# power.net
KiCad netlist of a schematic drawn in Altium Designer
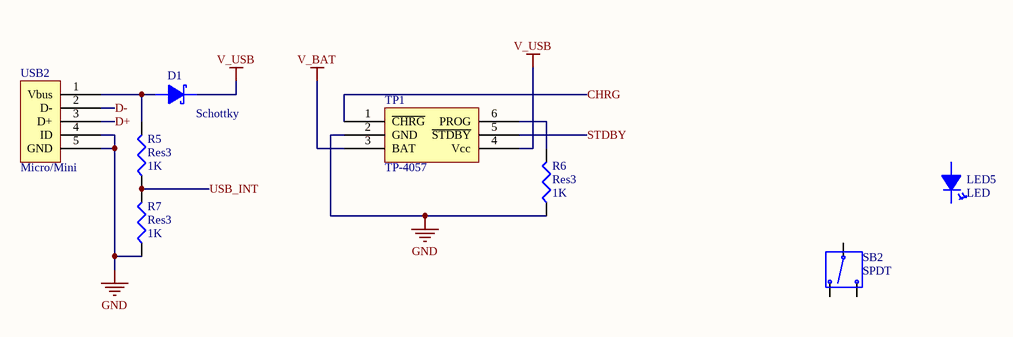
[diagram p0: power.SchDoc]

(export (version "E")
  (design (tool "Eeschema 10.0.6"))
  (components
    (comp (ref "D1") (value "Schottky") (footprint "SOD-523") (libsource (lib "ZGR") (part "Diode2")))
    (comp (ref "LED5") (value "LED") (footprint "LED_3mm_DIP") (libsource (lib "ZGR") (part "LED")))
    (comp (ref "R5")
      (value "Res3")
      (footprint "J1-0603")
      (description "Resistor")
      (fields (field (name "ALTIUM_VALUE") "1K") (field (name "PUBLISHER") "Altium Limited"))
      (libsource (lib "Miscellaneous Devices") (part "Res3"))
    )
    (comp (ref "R6")
      (value "Res3")
      (footprint "J1-0603")
      (description "Resistor")
      (fields (field (name "ALTIUM_VALUE") "1K") (field (name "PUBLISHER") "Altium Limited"))
      (libsource (lib "Miscellaneous Devices") (part "Res3"))
    )
    (comp (ref "R7")
      (value "Res3")
      (footprint "J1-0603")
      (description "Resistor")
      (fields (field (name "ALTIUM_VALUE") "1K") (field (name "PUBLISHER") "Altium Limited"))
      (libsource (lib "Miscellaneous Devices") (part "Res3"))
    )
    (comp (ref "SB2") (value "SPDT") (footprint "SS-SK-02P") (libsource (lib "ZGR") (part "Switch_Button2")))
    (comp (ref "TP1") (value "TP-4057") (footprint "SOT-23-6") (libsource (lib "ZGR") (part "TP-4057")))
    (comp (ref "USB2")
      (value "Micro/Mini")
      (footprint "USB_Micro-B_S_DIP_180")
      (libsource (lib "ZGR") (part "USB2"))
    )
  )
  (nets
    (net (code "1") (name "/CHRG") (class "Default")
      (node (ref "TP1") (pin "1") (pinfunction "~{CHRG}_1") (pintype "passive"))
    )
    (net (code "2") (name "/D+") (class "Default")
      (node (ref "USB2") (pin "3") (pinfunction "D+_3") (pintype "passive"))
    )
    (net (code "3") (name "/D-") (class "Default")
      (node (ref "USB2") (pin "2") (pinfunction "D-_2") (pintype "passive"))
    )
    (net (code "4") (name "/STDBY") (class "Default")
      (node (ref "TP1") (pin "5") (pinfunction "~{STDBY}_5") (pintype "passive"))
    )
    (net (code "5") (name "/USB_INT") (class "Default")
      (node (ref "R5") (pin "1") (pinfunction "1_1") (pintype "passive"))
      (node (ref "R7") (pin "2") (pinfunction "2_2") (pintype "passive"))
    )
    (net (code "6") (name "GND") (class "Default")
      (node (ref "R6") (pin "1") (pinfunction "1_1") (pintype "passive"))
      (node (ref "R7") (pin "1") (pinfunction "1_1") (pintype "passive"))
      (node (ref "TP1") (pin "2") (pinfunction "GND_2") (pintype "passive"))
      (node (ref "USB2") (pin "4") (pinfunction "ID_4") (pintype "passive"))
      (node (ref "USB2") (pin "5") (pinfunction "GND_5") (pintype "passive"))
    )
    (net (code "7") (name "Net-(TP1-PROG)") (class "Default")
      (node (ref "R6") (pin "2") (pinfunction "2_2") (pintype "passive"))
      (node (ref "TP1") (pin "6") (pinfunction "PROG_6") (pintype "passive"))
    )
    (net (code "8") (name "Net-(USB2-Vbus)") (class "Default")
      (node (ref "D1") (pin "1") (pinfunction "1_1") (pintype "passive"))
      (node (ref "R5") (pin "2") (pinfunction "2_2") (pintype "passive"))
      (node (ref "USB2") (pin "1") (pinfunction "Vbus_1") (pintype "passive"))
    )
    (net (code "9") (name "V_BAT") (class "Default")
      (node (ref "TP1") (pin "3") (pinfunction "BAT_3") (pintype "passive"))
    )
    (net (code "10") (name "V_USB") (class "Default")
      (node (ref "D1") (pin "2") (pinfunction "2_2") (pintype "passive"))
      (node (ref "TP1") (pin "4") (pinfunction "Vcc_4") (pintype "passive"))
    )
    (net (code "11") (name "unconnected-(LED5-Pad1)") (class "Default")
      (node (ref "LED5") (pin "1") (pinfunction "1_1") (pintype "passive"))
    )
    (net (code "12") (name "unconnected-(LED5-Pad2)") (class "Default")
      (node (ref "LED5") (pin "2") (pinfunction "2_2") (pintype "passive"))
    )
    (net (code "13") (name "unconnected-(SB2-Pad1)") (class "Default")
      (node (ref "SB2") (pin "1") (pinfunction "1_1") (pintype "passive"))
    )
    (net (code "14") (name "unconnected-(SB2-Pad2)") (class "Default")
      (node (ref "SB2") (pin "2") (pinfunction "2_2") (pintype "passive"))
    )
    (net (code "15") (name "unconnected-(SB2-Pad3)") (class "Default")
      (node (ref "SB2") (pin "3") (pinfunction "3_3") (pintype "passive"))
    )
  )
)
